# AVRProgrammer.net
KiCad netlist of a schematic drawn in EAGLE
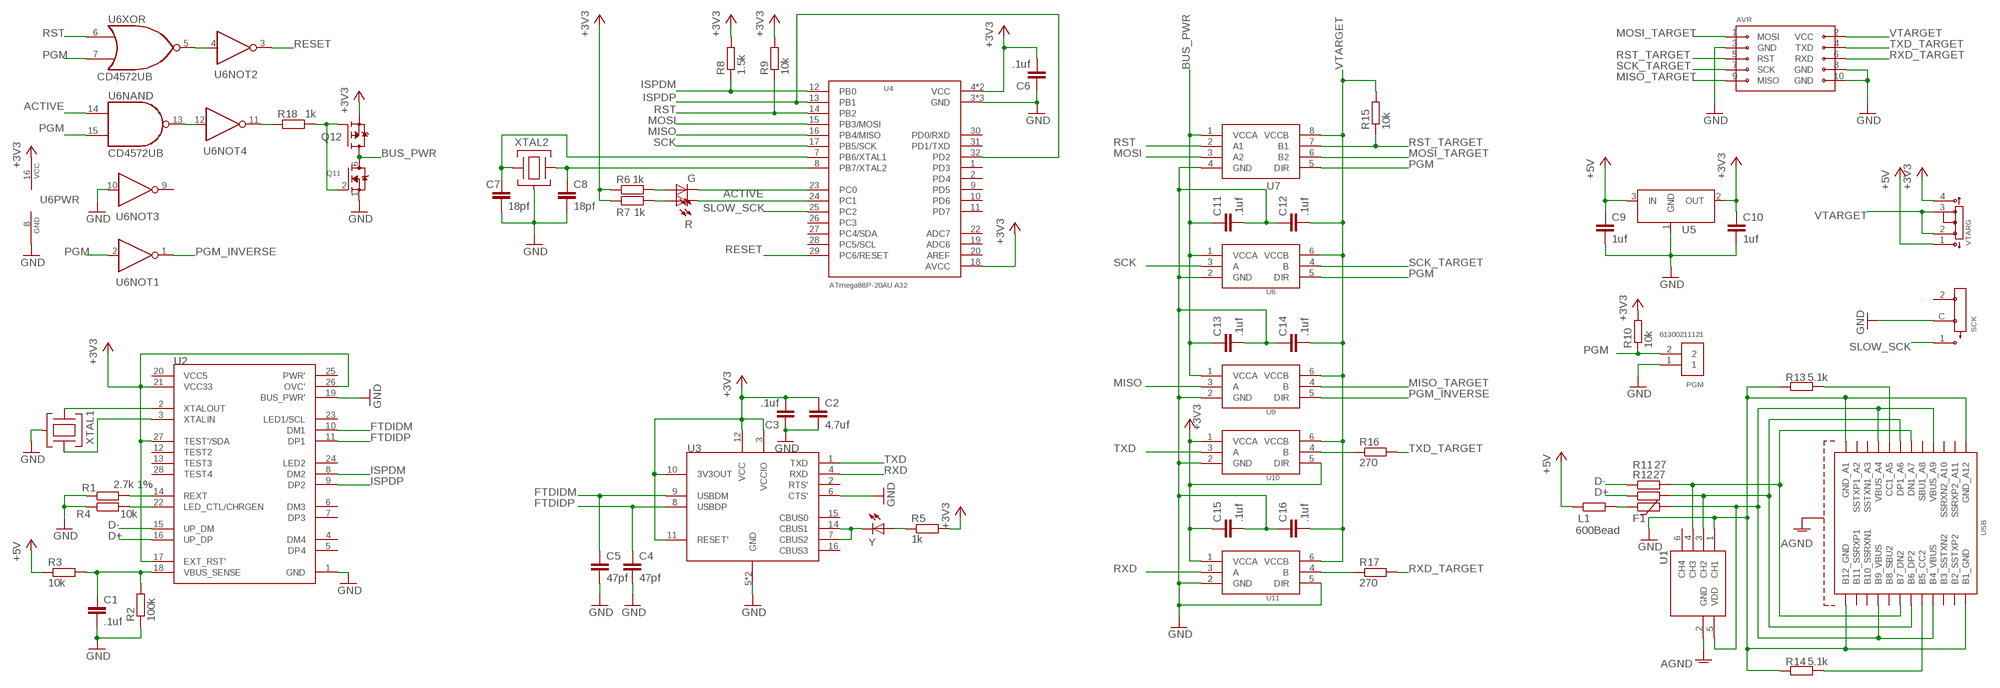
[diagram p0: schematic, sheet 1]

(export (version "E")
  (design (tool "Eeschema 10.0.6"))
  (components
    (comp (ref "AVR")
      (value "10PIN_ISP10PIN_ISP_RT")
      (footprint "eagle-import:10PIN_ISP_RT")
      (libsource (lib "eagle-import") (part "10PIN_ISP10PIN_ISP_RT"))
    )
    (comp (ref "C1")
      (value ".1uf")
      (footprint "eagle-import:C0805")
      (libsource (lib "eagle-import") (part "C-EUC0805"))
    )
    (comp (ref "C2")
      (value "4.7uf")
      (footprint "eagle-import:C0805")
      (libsource (lib "eagle-import") (part "C-EUC0805"))
    )
    (comp (ref "C3")
      (value ".1uf")
      (footprint "eagle-import:C0805")
      (libsource (lib "eagle-import") (part "C-EUC0805"))
    )
    (comp (ref "C4")
      (value "47pf")
      (footprint "eagle-import:C0805")
      (libsource (lib "eagle-import") (part "C-EUC0805"))
    )
    (comp (ref "C5")
      (value "47pf")
      (footprint "eagle-import:C0805")
      (libsource (lib "eagle-import") (part "C-EUC0805"))
    )
    (comp (ref "C6")
      (value ".1uf")
      (footprint "eagle-import:C0805")
      (libsource (lib "eagle-import") (part "C-EUC0805"))
    )
    (comp (ref "C7")
      (value "18pf")
      (footprint "eagle-import:C0805")
      (libsource (lib "eagle-import") (part "C-EUC0805"))
    )
    (comp (ref "C8")
      (value "18pf")
      (footprint "eagle-import:C0805")
      (libsource (lib "eagle-import") (part "C-EUC0805"))
    )
    (comp (ref "C9")
      (value "1uf")
      (footprint "eagle-import:C0805")
      (libsource (lib "eagle-import") (part "C-EUC0805"))
    )
    (comp (ref "C10")
      (value "1uf")
      (footprint "eagle-import:C0805")
      (libsource (lib "eagle-import") (part "C-EUC0805"))
    )
    (comp (ref "C11")
      (value ".1uf")
      (footprint "eagle-import:C0805")
      (libsource (lib "eagle-import") (part "C-EUC0805"))
    )
    (comp (ref "C12")
      (value ".1uf")
      (footprint "eagle-import:C0805")
      (libsource (lib "eagle-import") (part "C-EUC0805"))
    )
    (comp (ref "C13")
      (value ".1uf")
      (footprint "eagle-import:C0805")
      (libsource (lib "eagle-import") (part "C-EUC0805"))
    )
    (comp (ref "C14")
      (value ".1uf")
      (footprint "eagle-import:C0805")
      (libsource (lib "eagle-import") (part "C-EUC0805"))
    )
    (comp (ref "C15")
      (value ".1uf")
      (footprint "eagle-import:C0805")
      (libsource (lib "eagle-import") (part "C-EUC0805"))
    )
    (comp (ref "C16")
      (value ".1uf")
      (footprint "eagle-import:C0805")
      (libsource (lib "eagle-import") (part "C-EUC0805"))
    )
    (comp (ref "F1")
      (value "MF-PSHT035KX-2")
      (footprint "eagle-import:FUSC2113X120N")
      (libsource (lib "eagle-import") (part "PTC0805"))
    )
    (comp (ref "G")
      (value "SM0805GCL")
      (footprint "eagle-import:CHIPLED_0805")
      (libsource (lib "eagle-import") (part "LEDCHIPLED_0805"))
    )
    (comp (ref "L1")
      (value "600Bead")
      (footprint "eagle-import:M0805")
      (libsource (lib "eagle-import") (part "rcl_334_R-EU_M0805"))
    )
    (comp (ref "PGM")
      (value "61300211121")
      (footprint "eagle-import:61300211121")
      (fields
        (field (name "DIGI_KEY_PART_NUMBER") "732-5315-ND")
        (field (name "MANUFACTURER") "Wurth Electronics Inc.")
        (field (name "CREATED_BY") "PCBLayout.com")
      )
      (libsource (lib "eagle-import") (part "61300211121"))
    )
    (comp (ref "Q1")
      (value "SI1016CX-T1-GE3SOT-563F")
      (footprint "eagle-import:SOTFL50P160X60-6N")
      (libsource (lib "eagle-import") (part "SI1016CX-T1-GE3SOT-563F"))
    )
    (comp (ref "R")
      (value "SM0805HCL")
      (footprint "eagle-import:CHIPLED_0805")
      (libsource (lib "eagle-import") (part "LEDCHIPLED_0805"))
    )
    (comp (ref "R1")
      (value "2.7k 1%")
      (footprint "eagle-import:M0805")
      (libsource (lib "eagle-import") (part "rcl_334_R-EU_M0805"))
    )
    (comp (ref "R2")
      (value "100k")
      (footprint "eagle-import:M0805")
      (libsource (lib "eagle-import") (part "rcl_334_R-EU_M0805"))
    )
    (comp (ref "R3")
      (value "10k")
      (footprint "eagle-import:M0805")
      (libsource (lib "eagle-import") (part "rcl_334_R-EU_M0805"))
    )
    (comp (ref "R4")
      (value "10k")
      (footprint "eagle-import:M0805")
      (libsource (lib "eagle-import") (part "R-EU_M0805"))
    )
    (comp (ref "R5")
      (value "1k")
      (footprint "eagle-import:M0805")
      (libsource (lib "eagle-import") (part "rcl_334_R-EU_M0805"))
    )
    (comp (ref "R6")
      (value "1k")
      (footprint "eagle-import:M0805")
      (libsource (lib "eagle-import") (part "rcl_334_R-EU_M0805"))
    )
    (comp (ref "R7")
      (value "1k")
      (footprint "eagle-import:M0805")
      (libsource (lib "eagle-import") (part "rcl_334_R-EU_M0805"))
    )
    (comp (ref "R8")
      (value "1.5k")
      (footprint "eagle-import:M0805")
      (libsource (lib "eagle-import") (part "R-EU_M0805"))
    )
    (comp (ref "R9")
      (value "10k")
      (footprint "eagle-import:M0805")
      (libsource (lib "eagle-import") (part "R-EU_M0805"))
    )
    (comp (ref "R10")
      (value "10k")
      (footprint "eagle-import:R0805")
      (libsource (lib "eagle-import") (part "rcl_334_R-EU_R0805"))
    )
    (comp (ref "R11")
      (value "27")
      (footprint "eagle-import:M0805")
      (libsource (lib "eagle-import") (part "rcl_334_R-EU_M0805"))
    )
    (comp (ref "R12")
      (value "27")
      (footprint "eagle-import:M0805")
      (libsource (lib "eagle-import") (part "rcl_334_R-EU_M0805"))
    )
    (comp (ref "R13")
      (value "5.1k")
      (footprint "eagle-import:M0805")
      (libsource (lib "eagle-import") (part "rcl_334_R-EU_M0805"))
    )
    (comp (ref "R14")
      (value "5.1k")
      (footprint "eagle-import:M0805")
      (libsource (lib "eagle-import") (part "rcl_334_R-EU_M0805"))
    )
    (comp (ref "R15")
      (value "10k")
      (footprint "eagle-import:R0805")
      (libsource (lib "eagle-import") (part "rcl_334_R-EU_R0805"))
    )
    (comp (ref "R16")
      (value "270")
      (footprint "eagle-import:R0805")
      (libsource (lib "eagle-import") (part "rcl_334_R-EU_R0805"))
    )
    (comp (ref "R17")
      (value "270")
      (footprint "eagle-import:R0805")
      (libsource (lib "eagle-import") (part "rcl_334_R-EU_R0805"))
    )
    (comp (ref "R18")
      (value "1k")
      (footprint "eagle-import:M0805")
      (libsource (lib "eagle-import") (part "rcl_334_R-EU_M0805"))
    )
    (comp (ref "SCK")
      (value "SPDT_SWITCH")
      (footprint "eagle-import:SSAJ110100")
      (libsource (lib "eagle-import") (part "SPDT_SWITCH"))
    )
    (comp (ref "U1")
      (value "D5V0F4U6SO")
      (footprint "eagle-import:SOT95P280X145-6")
      (libsource (lib "eagle-import") (part "D5V0F4U6SO"))
    )
    (comp (ref "U2")
      (value "XR22404SSOP28")
      (footprint "eagle-import:SOP63P599X173-28")
      (libsource (lib "eagle-import") (part "XR22404SSOP28"))
    )
    (comp (ref "U3")
      (value "FT230XSSOP16")
      (footprint "eagle-import:SOP63P599X175-16")
      (libsource (lib "eagle-import") (part "FT230XSSOP16"))
    )
    (comp (ref "U4")
      (value "ATmega88P-20AU A32")
      (footprint "eagle-import:QFP80P887X887X120-32")
      (libsource (lib "eagle-import") (part "ATMEGA328P-AUTQFP-32"))
    )
    (comp (ref "U5")
      (value "AZ1117E-3.3SOT-223")
      (footprint "eagle-import:SOT230P700X180-4")
      (libsource (lib "eagle-import") (part "AZ1117E-3.3SOT-223"))
    )
    (comp (ref "U6")
      (value "CD4572UB")
      (footprint "eagle-import:SOP65P640X110-16N")
      (libsource (lib "eagle-import") (part "CD4572UB"))
    )
    (comp (ref "U7")
      (value "SN74LVC2T45-Q1VSSOP-8")
      (footprint "eagle-import:SOP50P310X90-8N")
      (libsource (lib "eagle-import") (part "SN74LVC2T45-Q1VSSOP-8"))
    )
    (comp (ref "U8")
      (value "SN74LVC1T45DRL")
      (footprint "eagle-import:SOTFL50P160X60-6N")
      (libsource (lib "eagle-import") (part "SN74LVC1T45DRL"))
    )
    (comp (ref "U9")
      (value "SN74LVC1T45DRL")
      (footprint "eagle-import:SOTFL50P160X60-6N")
      (libsource (lib "eagle-import") (part "SN74LVC1T45DRL"))
    )
    (comp (ref "U10")
      (value "SN74LVC1T45DRL")
      (footprint "eagle-import:SOTFL50P160X60-6N")
      (libsource (lib "eagle-import") (part "SN74LVC1T45DRL"))
    )
    (comp (ref "U11")
      (value "SN74LVC1T45DRL")
      (footprint "eagle-import:SOTFL50P160X60-6N")
      (libsource (lib "eagle-import") (part "SN74LVC1T45DRL"))
    )
    (comp (ref "USB")
      (value "USBC_FEMALEUJ31-CH-G2-SMT-TR")
      (footprint "eagle-import:USBC_UJ31-CH-G2-SMT-TR")
      (libsource (lib "eagle-import") (part "USBC_FEMALEUJ31-CH-G2-SMT-TR"))
    )
    (comp (ref "VTARG")
      (value "SP3T_SWITCH")
      (footprint "eagle-import:EG1315AA")
      (libsource (lib "eagle-import") (part "SP3T_SWITCH"))
    )
    (comp (ref "XTAL1")
      (value "XTAL_ABM8AIG")
      (footprint "eagle-import:XTAL_SMT_3.2X2.5")
      (libsource (lib "eagle-import") (part "XTAL_ABM8AIG"))
    )
    (comp (ref "XTAL2")
      (value "XTAL_ABM8AIG")
      (footprint "eagle-import:XTAL_SMT_3.2X2.5")
      (libsource (lib "eagle-import") (part "XTAL_ABM8AIG"))
    )
    (comp (ref "Y")
      (value "LEDCHIPLED_0805")
      (footprint "eagle-import:CHIPLED_0805")
      (libsource (lib "eagle-import") (part "LEDCHIPLED_0805"))
    )
  )
  (nets
    (net (code "1") (name "+3V3") (class "Default")
      (node (ref "C10") (pin "1") (pinfunction "1_1") (pintype "passive"))
      (node (ref "C15") (pin "1") (pinfunction "1_1") (pintype "passive"))
      (node (ref "C2") (pin "1") (pinfunction "1_1") (pintype "passive"))
      (node (ref "C3") (pin "2") (pinfunction "2_2") (pintype "passive"))
      (node (ref "C6") (pin "2") (pinfunction "2_2") (pintype "passive"))
      (node (ref "Q1") (pin "4") (pinfunction "S_4") (pintype "passive"))
      (node (ref "R10") (pin "2") (pinfunction "2_2") (pintype "passive"))
      (node (ref "R5") (pin "2") (pinfunction "2_2") (pintype "passive"))
      (node (ref "R6") (pin "1") (pinfunction "1_1") (pintype "passive"))
      (node (ref "R7") (pin "1") (pinfunction "1_1") (pintype "passive"))
      (node (ref "R8") (pin "2") (pinfunction "2_2") (pintype "passive"))
      (node (ref "R9") (pin "2") (pinfunction "2_2") (pintype "passive"))
      (node (ref "U10") (pin "1") (pinfunction "VCCA_1") (pintype "power_in"))
      (node (ref "U10") (pin "5") (pinfunction "DIR_5") (pintype "bidirectional"))
      (node (ref "U11") (pin "1") (pinfunction "VCCA_1") (pintype "power_in"))
      (node (ref "U2") (pin "17") (pinfunction "EXT_RST'_17") (pintype "bidirectional"))
      (node (ref "U2") (pin "21") (pinfunction "VCC33_21") (pintype "bidirectional"))
      (node (ref "U2") (pin "26") (pinfunction "OVC'_26") (pintype "bidirectional"))
      (node (ref "U2") (pin "27") (pinfunction "TEST'/SDA_27") (pintype "bidirectional"))
      (node (ref "U3") (pin "10") (pinfunction "3V3OUT_10") (pintype "bidirectional"))
      (node (ref "U3") (pin "11") (pinfunction "RESET'_11") (pintype "bidirectional"))
      (node (ref "U3") (pin "12") (pinfunction "VCC_12") (pintype "power_in"))
      (node (ref "U3") (pin "3") (pinfunction "VCCIO_3") (pintype "power_in"))
      (node (ref "U4") (pin "18") (pinfunction "AVCC_18") (pintype "power_in"))
      (node (ref "U4") (pin "4") (pinfunction "VCC_4") (pintype "power_in"))
      (node (ref "U4") (pin "6") (pinfunction "VCC_6") (pintype "power_in"))
      (node (ref "U5") (pin "2") (pinfunction "OUT_2") (pintype "power_in"))
      (node (ref "U6") (pin "16") (pinfunction "VCC_16") (pintype "power_in"))
      (node (ref "VTARG") (pin "4") (pinfunction "4_4") (pintype "bidirectional"))
    )
    (net (code "2") (name "+5V") (class "Default")
      (node (ref "C9") (pin "1") (pinfunction "1_1") (pintype "passive"))
      (node (ref "L1") (pin "1") (pinfunction "1_1") (pintype "passive"))
      (node (ref "R3") (pin "1") (pinfunction "1_1") (pintype "passive"))
      (node (ref "U5") (pin "3") (pinfunction "IN_3") (pintype "power_in"))
      (node (ref "VTARG") (pin "1") (pinfunction "1_1") (pintype "bidirectional"))
    )
    (net (code "3") (name "/ACTIVE") (class "Default")
      (node (ref "R") (pin "C") (pinfunction "C_C") (pintype "passive"))
      (node (ref "U4") (pin "24") (pinfunction "PC1_24") (pintype "bidirectional"))
      (node (ref "U6") (pin "14") (pinfunction "I0_14") (pintype "input"))
    )
    (net (code "4") (name "/BUS_PWR") (class "Default")
      (node (ref "C11") (pin "1") (pinfunction "1_1") (pintype "passive"))
      (node (ref "C13") (pin "1") (pinfunction "1_1") (pintype "passive"))
      (node (ref "Q1") (pin "3") (pinfunction "D_3") (pintype "passive"))
      (node (ref "Q1") (pin "6") (pinfunction "D_6") (pintype "bidirectional"))
      (node (ref "U7") (pin "1") (pinfunction "VCCA_1") (pintype "power_in"))
      (node (ref "U8") (pin "1") (pinfunction "VCCA_1") (pintype "power_in"))
      (node (ref "U9") (pin "1") (pinfunction "VCCA_1") (pintype "power_in"))
    )
    (net (code "5") (name "/D+") (class "Default")
      (node (ref "R12") (pin "1") (pinfunction "1_1") (pintype "passive"))
      (node (ref "U2") (pin "16") (pinfunction "UP_DP_16") (pintype "bidirectional"))
    )
    (net (code "6") (name "/D-") (class "Default")
      (node (ref "R11") (pin "1") (pinfunction "1_1") (pintype "passive"))
      (node (ref "U2") (pin "15") (pinfunction "UP_DM_15") (pintype "bidirectional"))
    )
    (net (code "7") (name "/FTDIDM") (class "Default")
      (node (ref "C5") (pin "1") (pinfunction "1_1") (pintype "passive"))
      (node (ref "U2") (pin "10") (pinfunction "DM1_10") (pintype "bidirectional"))
      (node (ref "U3") (pin "9") (pinfunction "USBDM_9") (pintype "bidirectional"))
    )
    (net (code "8") (name "/FTDIDP") (class "Default")
      (node (ref "C4") (pin "1") (pinfunction "1_1") (pintype "passive"))
      (node (ref "U2") (pin "11") (pinfunction "DP1_11") (pintype "bidirectional"))
      (node (ref "U3") (pin "8") (pinfunction "USBDP_8") (pintype "bidirectional"))
    )
    (net (code "9") (name "/ISPDM") (class "Default")
      (node (ref "R8") (pin "1") (pinfunction "1_1") (pintype "passive"))
      (node (ref "U2") (pin "8") (pinfunction "DM2_8") (pintype "bidirectional"))
      (node (ref "U4") (pin "12") (pinfunction "PB0_12") (pintype "bidirectional"))
    )
    (net (code "10") (name "/ISPDP") (class "Default")
      (node (ref "U2") (pin "9") (pinfunction "DP2_9") (pintype "bidirectional"))
      (node (ref "U4") (pin "13") (pinfunction "PB1_13") (pintype "bidirectional"))
      (node (ref "U4") (pin "32") (pinfunction "PD2_32") (pintype "bidirectional"))
    )
    (net (code "11") (name "/MISO") (class "Default")
      (node (ref "U4") (pin "16") (pinfunction "PB4/MISO_16") (pintype "bidirectional"))
      (node (ref "U9") (pin "3") (pinfunction "A_3") (pintype "bidirectional"))
    )
    (net (code "12") (name "/MISO_TARGET") (class "Default")
      (node (ref "AVR") (pin "9") (pinfunction "MISO_9") (pintype "bidirectional"))
      (node (ref "U9") (pin "4") (pinfunction "B_4") (pintype "bidirectional"))
    )
    (net (code "13") (name "/MOSI") (class "Default")
      (node (ref "U4") (pin "15") (pinfunction "PB3/MOSI_15") (pintype "bidirectional"))
      (node (ref "U7") (pin "3") (pinfunction "A2_3") (pintype "bidirectional"))
    )
    (net (code "14") (name "/MOSI_TARGET") (class "Default")
      (node (ref "AVR") (pin "1") (pinfunction "MOSI_1") (pintype "bidirectional"))
      (node (ref "U7") (pin "6") (pinfunction "B2_6") (pintype "bidirectional"))
    )
    (net (code "15") (name "/PGM") (class "Default")
      (node (ref "PGM") (pin "2") (pinfunction "2_2") (pintype "passive"))
      (node (ref "R10") (pin "1") (pinfunction "1_1") (pintype "passive"))
      (node (ref "U6") (pin "15") (pinfunction "I1_15") (pintype "input"))
      (node (ref "U6") (pin "2") (pinfunction "A_2") (pintype "bidirectional"))
      (node (ref "U6") (pin "7") (pinfunction "I1_7") (pintype "input"))
      (node (ref "U7") (pin "5") (pinfunction "DIR_5") (pintype "bidirectional"))
      (node (ref "U8") (pin "5") (pinfunction "DIR_5") (pintype "bidirectional"))
    )
    (net (code "16") (name "/PGM_INVERSE") (class "Default")
      (node (ref "U6") (pin "1") (pinfunction "Y_1") (pintype "bidirectional"))
      (node (ref "U9") (pin "5") (pinfunction "DIR_5") (pintype "bidirectional"))
    )
    (net (code "17") (name "/RESET") (class "Default")
      (node (ref "U4") (pin "29") (pinfunction "PC6/RESET_29") (pintype "bidirectional"))
      (node (ref "U6") (pin "3") (pinfunction "Y_3") (pintype "bidirectional"))
    )
    (net (code "18") (name "/RST") (class "Default")
      (node (ref "R9") (pin "1") (pinfunction "1_1") (pintype "passive"))
      (node (ref "U4") (pin "14") (pinfunction "PB2_14") (pintype "bidirectional"))
      (node (ref "U6") (pin "6") (pinfunction "I0_6") (pintype "input"))
      (node (ref "U7") (pin "2") (pinfunction "A1_2") (pintype "bidirectional"))
    )
    (net (code "19") (name "/RST_TARGET") (class "Default")
      (node (ref "AVR") (pin "5") (pinfunction "RST_5") (pintype "bidirectional"))
      (node (ref "R15") (pin "1") (pinfunction "1_1") (pintype "passive"))
      (node (ref "U7") (pin "7") (pinfunction "B1_7") (pintype "bidirectional"))
    )
    (net (code "20") (name "/RXD") (class "Default")
      (node (ref "U11") (pin "3") (pinfunction "A_3") (pintype "bidirectional"))
      (node (ref "U3") (pin "4") (pinfunction "RXD_4") (pintype "bidirectional"))
    )
    (net (code "21") (name "/RXD_TARGET") (class "Default")
      (node (ref "AVR") (pin "6") (pinfunction "RXD_6") (pintype "bidirectional"))
      (node (ref "R17") (pin "2") (pinfunction "2_2") (pintype "passive"))
    )
    (net (code "22") (name "/SCK") (class "Default")
      (node (ref "U4") (pin "17") (pinfunction "PB5/SCK_17") (pintype "bidirectional"))
      (node (ref "U8") (pin "3") (pinfunction "A_3") (pintype "bidirectional"))
    )
    (net (code "23") (name "/SCK_TARGET") (class "Default")
      (node (ref "AVR") (pin "7") (pinfunction "SCK_7") (pintype "bidirectional"))
      (node (ref "U8") (pin "4") (pinfunction "B_4") (pintype "bidirectional"))
    )
    (net (code "24") (name "/SLOW_SCK") (class "Default")
      (node (ref "SCK") (pin "1") (pinfunction "1_1") (pintype "bidirectional"))
      (node (ref "U4") (pin "25") (pinfunction "PC2_25") (pintype "bidirectional"))
    )
    (net (code "25") (name "/TXD") (class "Default")
      (node (ref "U10") (pin "3") (pinfunction "A_3") (pintype "bidirectional"))
      (node (ref "U3") (pin "1") (pinfunction "TXD_1") (pintype "bidirectional"))
    )
    (net (code "26") (name "/TXD_TARGET") (class "Default")
      (node (ref "AVR") (pin "4") (pinfunction "TXD_4") (pintype "bidirectional"))
      (node (ref "R16") (pin "2") (pinfunction "2_2") (pintype "passive"))
    )
    (net (code "27") (name "/VCC5") (class "Default")
      (node (ref "U2") (pin "20") (pinfunction "VCC5_20") (pintype "power_in"))
    )
    (net (code "28") (name "/VTARGET") (class "Default")
      (node (ref "AVR") (pin "2") (pinfunction "VCC_2") (pintype "bidirectional"))
      (node (ref "C12") (pin "2") (pinfunction "2_2") (pintype "passive"))
      (node (ref "C14") (pin "2") (pinfunction "2_2") (pintype "passive"))
      (node (ref "C16") (pin "2") (pinfunction "2_2") (pintype "passive"))
      (node (ref "R15") (pin "2") (pinfunction "2_2") (pintype "passive"))
      (node (ref "U10") (pin "6") (pinfunction "VCCB_6") (pintype "power_in"))
      (node (ref "U11") (pin "6") (pinfunction "VCCB_6") (pintype "power_in"))
      (node (ref "U7") (pin "8") (pinfunction "VCCB_8") (pintype "power_in"))
      (node (ref "U8") (pin "6") (pinfunction "VCCB_6") (pintype "power_in"))
      (node (ref "U9") (pin "6") (pinfunction "VCCB_6") (pintype "power_in"))
      (node (ref "VTARG") (pin "2") (pinfunction "2_2") (pintype "bidirectional"))
      (node (ref "VTARG") (pin "3") (pinfunction "C_3") (pintype "bidirectional"))
    )
    (net (code "29") (name "AGND") (class "Default")
      (node (ref "U1") (pin "2") (pinfunction "GND_2") (pintype "bidirectional"))
      (node (ref "USB") (pin "SHD$1") (pinfunction "SHLD_SHD$1") (pintype "power_in"))
      (node (ref "USB") (pin "SHD$2") (pinfunction "SHLD_SHD$2") (pintype "power_in"))
      (node (ref "USB") (pin "SHD$3") (pinfunction "SHLD_SHD$3") (pintype "power_in"))
      (node (ref "USB") (pin "SHD$4") (pinfunction "SHLD_SHD$4") (pintype "power_in"))
    )
    (net (code "30") (name "GND") (class "Default")
      (node (ref "AVR") (pin "10") (pinfunction "GND_10") (pintype "bidirectional"))
      (node (ref "AVR") (pin "3") (pinfunction "GND_3") (pintype "bidirectional"))
      (node (ref "AVR") (pin "8") (pinfunction "GND_8") (pintype "bidirectional"))
      (node (ref "C1") (pin "2") (pinfunction "2_2") (pintype "passive"))
      (node (ref "C10") (pin "2") (pinfunction "2_2") (pintype "passive"))
      (node (ref "C11") (pin "2") (pinfunction "2_2") (pintype "passive"))
      (node (ref "C12") (pin "1") (pinfunction "1_1") (pintype "passive"))
      (node (ref "C13") (pin "2") (pinfunction "2_2") (pintype "passive"))
      (node (ref "C14") (pin "1") (pinfunction "1_1") (pintype "passive"))
      (node (ref "C15") (pin "2") (pinfunction "2_2") (pintype "passive"))
      (node (ref "C16") (pin "1") (pinfunction "1_1") (pintype "passive"))
      (node (ref "C2") (pin "2") (pinfunction "2_2") (pintype "passive"))
      (node (ref "C3") (pin "1") (pinfunction "1_1") (pintype "passive"))
      (node (ref "C4") (pin "2") (pinfunction "2_2") (pintype "passive"))
      (node (ref "C5") (pin "2") (pinfunction "2_2") (pintype "passive"))
      (node (ref "C6") (pin "1") (pinfunction "1_1") (pintype "passive"))
      (node (ref "C7") (pin "2") (pinfunction "2_2") (pintype "passive"))
      (node (ref "C8") (pin "2") (pinfunction "2_2") (pintype "passive"))
      (node (ref "C9") (pin "2") (pinfunction "2_2") (pintype "passive"))
      (node (ref "PGM") (pin "1") (pinfunction "1_1") (pintype "passive"))
      (node (ref "Q1") (pin "1") (pinfunction "S_1") (pintype "bidirectional"))
      (node (ref "R1") (pin "1") (pinfunction "1_1") (pintype "passive"))
      (node (ref "R13") (pin "1") (pinfunction "1_1") (pintype "passive"))
      (node (ref "R14") (pin "1") (pinfunction "1_1") (pintype "passive"))
      (node (ref "R2") (pin "1") (pinfunction "1_1") (pintype "passive"))
      (node (ref "R4") (pin "1") (pinfunction "1_1") (pintype "passive"))
      (node (ref "SCK") (pin "C") (pinfunction "C_C") (pintype "bidirectional"))
      (node (ref "U1") (pin "1") (pinfunction "CH1_1") (pintype "bidirectional"))
      (node (ref "U10") (pin "2") (pinfunction "GND_2") (pintype "power_in"))
      (node (ref "U11") (pin "2") (pinfunction "GND_2") (pintype "power_in"))
      (node (ref "U11") (pin "5") (pinfunction "DIR_5") (pintype "bidirectional"))
      (node (ref "U2") (pin "1") (pinfunction "GND_1") (pintype "power_in"))
      (node (ref "U2") (pin "19") (pinfunction "BUS_PWR'_19") (pintype "bidirectional"))
      (node (ref "U3") (pin "13") (pinfunction "GND_13") (pintype "power_in"))
      (node (ref "U3") (pin "5") (pinfunction "GND_5") (pintype "power_in"))
      (node (ref "U3") (pin "6") (pinfunction "CTS'_6") (pintype "bidirectional"))
      (node (ref "U4") (pin "21") (pinfunction "GND_21") (pintype "power_in"))
      (node (ref "U4") (pin "3") (pinfunction "GND_3") (pintype "power_in"))
      (node (ref "U4") (pin "5") (pinfunction "GND_5") (pintype "power_in"))
      (node (ref "U5") (pin "1") (pinfunction "GND_1") (pintype "power_in"))
      (node (ref "U6") (pin "10") (pinfunction "A_10") (pintype "bidirectional"))
      (node (ref "U6") (pin "8") (pinfunction "GND_8") (pintype "power_in"))
      (node (ref "U7") (pin "4") (pinfunction "GND_4") (pintype "power_in"))
      (node (ref "U8") (pin "2") (pinfunction "GND_2") (pintype "power_in"))
      (node (ref "U9") (pin "2") (pinfunction "GND_2") (pintype "power_in"))
      (node (ref "USB") (pin "A1") (pinfunction "GND_A1_A1") (pintype "power_in"))
      (node (ref "USB") (pin "A12") (pinfunction "GND_A12_A12") (pintype "power_in"))
      (node (ref "USB") (pin "B1") (pinfunction "B1_GND_B1") (pintype "power_in"))
      (node (ref "USB") (pin "B12") (pinfunction "B12_GND_B12") (pintype "power_in"))
      (node (ref "XTAL1") (pin "2") (pinfunction "CASE_2") (pintype "bidirectional"))
      (node (ref "XTAL1") (pin "4") (pinfunction "CASE_4") (pintype "bidirectional"))
      (node (ref "XTAL2") (pin "2") (pinfunction "CASE_2") (pintype "bidirectional"))
      (node (ref "XTAL2") (pin "4") (pinfunction "CASE_4") (pintype "bidirectional"))
    )
    (net (code "31") (name "Net-(F1-Pad1)") (class "Default")
      (node (ref "F1") (pin "1") (pinfunction "1_1") (pintype "passive"))
      (node (ref "L1") (pin "2") (pinfunction "2_2") (pintype "passive"))
    )
    (net (code "32") (name "Net-(G-PadA)") (class "Default")
      (node (ref "G") (pin "A") (pinfunction "A_A") (pintype "passive"))
      (node (ref "R6") (pin "2") (pinfunction "2_2") (pintype "passive"))
    )
    (net (code "33") (name "Net-(Q1A-G)") (class "Default")
      (node (ref "Q1") (pin "2") (pinfunction "G_2") (pintype "bidirectional"))
      (node (ref "Q1") (pin "5") (pinfunction "G_5") (pintype "passive"))
      (node (ref "R18") (pin "2") (pinfunction "2_2") (pintype "passive"))
    )
    (net (code "34") (name "Net-(R-PadA)") (class "Default")
      (node (ref "R") (pin "A") (pinfunction "A_A") (pintype "passive"))
      (node (ref "R7") (pin "2") (pinfunction "2_2") (pintype "passive"))
    )
    (net (code "35") (name "Net-(R5-Pad1)") (class "Default")
      (node (ref "R5") (pin "1") (pinfunction "1_1") (pintype "passive"))
      (node (ref "Y") (pin "A") (pinfunction "A_A") (pintype "passive"))
    )
    (net (code "36") (name "Net-(U1-CH2)") (class "Default")
      (node (ref "R12") (pin "2") (pinfunction "2_2") (pintype "passive"))
      (node (ref "U1") (pin "3") (pinfunction "CH2_3") (pintype "bidirectional"))
      (node (ref "USB") (pin "A6") (pinfunction "DP1_A6_A6") (pintype "bidirectional"))
      (node (ref "USB") (pin "B6") (pinfunction "B6_DP2_B6") (pintype "bidirectional"))
    )
    (net (code "37") (name "Net-(U1-CH3)") (class "Default")
      (node (ref "R11") (pin "2") (pinfunction "2_2") (pintype "passive"))
      (node (ref "U1") (pin "4") (pinfunction "CH3_4") (pintype "bidirectional"))
      (node (ref "USB") (pin "A7") (pinfunction "DN1_A7_A7") (pintype "bidirectional"))
      (node (ref "USB") (pin "B7") (pinfunction "B7_DN2_B7") (pintype "bidirectional"))
    )
    (net (code "38") (name "Net-(U1-VDD)") (class "Default")
      (node (ref "F1") (pin "2") (pinfunction "2_2") (pintype "passive"))
      (node (ref "U1") (pin "5") (pinfunction "VDD_5") (pintype "bidirectional"))
      (node (ref "USB") (pin "A4") (pinfunction "VBUS_A4_A4") (pintype "power_in"))
      (node (ref "USB") (pin "A9") (pinfunction "VBUS_A9_A9") (pintype "power_in"))
      (node (ref "USB") (pin "B4") (pinfunction "B4_VBUS_B4") (pintype "power_in"))
      (node (ref "USB") (pin "B9") (pinfunction "B9_VBUS_B9") (pintype "power_in"))
    )
    (net (code "39") (name "Net-(U2-LED_CTL{slash}CHRGEN)") (class "Default")
      (node (ref "R4") (pin "2") (pinfunction "2_2") (pintype "passive"))
      (node (ref "U2") (pin "22") (pinfunction "LED_CTL/CHRGEN_22") (pintype "bidirectional"))
    )
    (net (code "40") (name "Net-(U2-REXT)") (class "Default")
      (node (ref "R1") (pin "2") (pinfunction "2_2") (pintype "passive"))
      (node (ref "U2") (pin "14") (pinfunction "REXT_14") (pintype "bidirectional"))
    )
    (net (code "41") (name "Net-(U2-VBUS_SENSE)") (class "Default")
      (node (ref "C1") (pin "1") (pinfunction "1_1") (pintype "passive"))
      (node (ref "R2") (pin "2") (pinfunction "2_2") (pintype "passive"))
      (node (ref "R3") (pin "2") (pinfunction "2_2") (pintype "passive"))
      (node (ref "U2") (pin "18") (pinfunction "VBUS_SENSE_18") (pintype "bidirectional"))
    )
    (net (code "42") (name "Net-(U2-XTALIN)") (class "Default")
      (node (ref "U2") (pin "3") (pinfunction "XTALIN_3") (pintype "bidirectional"))
      (node (ref "XTAL1") (pin "3") (pinfunction "P$2_3") (pintype "bidirectional"))
    )
    (net (code "43") (name "Net-(U2-XTALOUT)") (class "Default")
      (node (ref "U2") (pin "2") (pinfunction "XTALOUT_2") (pintype "bidirectional"))
      (node (ref "XTAL1") (pin "1") (pinfunction "P$1_1") (pintype "bidirectional"))
    )
    (net (code "44") (name "Net-(U3-CBUS1)") (class "Default")
      (node (ref "U3") (pin "14") (pinfunction "CBUS1_14") (pintype "bidirectional"))
      (node (ref "U3") (pin "7") (pinfunction "CBUS2_7") (pintype "bidirectional"))
      (node (ref "Y") (pin "C") (pinfunction "C_C") (pintype "passive"))
    )
    (net (code "45") (name "Net-(U4-PB6{slash}XTAL1)") (class "Default")
      (node (ref "C7") (pin "1") (pinfunction "1_1") (pintype "passive"))
      (node (ref "U4") (pin "7") (pinfunction "PB6/XTAL1_7") (pintype "bidirectional"))
      (node (ref "XTAL2") (pin "1") (pinfunction "P$1_1") (pintype "bidirectional"))
    )
    (net (code "46") (name "Net-(U4-PB7{slash}XTAL2)") (class "Default")
      (node (ref "C8") (pin "1") (pinfunction "1_1") (pintype "passive"))
      (node (ref "U4") (pin "8") (pinfunction "PB7/XTAL2_8") (pintype "bidirectional"))
      (node (ref "XTAL2") (pin "3") (pinfunction "P$2_3") (pintype "bidirectional"))
    )
    (net (code "47") (name "Net-(U4-PC0)") (class "Default")
      (node (ref "G") (pin "C") (pinfunction "C_C") (pintype "passive"))
      (node (ref "U4") (pin "23") (pinfunction "PC0_23") (pintype "bidirectional"))
    )
    (net (code "48") (name "Net-(U6A-O)") (class "Default")
      (node (ref "U6") (pin "12") (pinfunction "A_12") (pintype "bidirectional"))
      (node (ref "U6") (pin "13") (pinfunction "O_13") (pintype "output"))
    )
    (net (code "49") (name "Net-(U6C-A)") (class "Default")
      (node (ref "U6") (pin "4") (pinfunction "A_4") (pintype "bidirectional"))
      (node (ref "U6") (pin "5") (pinfunction "O_5") (pintype "output"))
    )
    (net (code "50") (name "Net-(U6E-Y)") (class "Default")
      (node (ref "R18") (pin "1") (pinfunction "1_1") (pintype "passive"))
      (node (ref "U6") (pin "11") (pinfunction "Y_11") (pintype "bidirectional"))
    )
    (net (code "51") (name "Net-(U10-B)") (class "Default")
      (node (ref "R16") (pin "1") (pinfunction "1_1") (pintype "passive"))
      (node (ref "U10") (pin "4") (pinfunction "B_4") (pintype "bidirectional"))
    )
    (net (code "52") (name "Net-(U11-B)") (class "Default")
      (node (ref "R17") (pin "1") (pinfunction "1_1") (pintype "passive"))
      (node (ref "U11") (pin "4") (pinfunction "B_4") (pintype "bidirectional"))
    )
    (net (code "53") (name "Net-(USB-B5_CC2)") (class "Default")
      (node (ref "R14") (pin "2") (pinfunction "2_2") (pintype "passive"))
      (node (ref "USB") (pin "B5") (pinfunction "B5_CC2_B5") (pintype "bidirectional"))
    )
    (net (code "54") (name "Net-(USB-CC1_A5)") (class "Default")
      (node (ref "R13") (pin "2") (pinfunction "2_2") (pintype "passive"))
      (node (ref "USB") (pin "A5") (pinfunction "CC1_A5_A5") (pintype "bidirectional"))
    )
    (net (code "55") (name "unconnected-(SCK-Pad2)") (class "Default")
      (node (ref "SCK") (pin "2") (pinfunction "2_2") (pintype "bidirectional"))
    )
    (net (code "56") (name "unconnected-(U1-CH4-Pad6)") (class "Default")
      (node (ref "U1") (pin "6") (pinfunction "CH4_6") (pintype "bidirectional"))
    )
    (net (code "57") (name "unconnected-(U2-DM3-Pad6)") (class "Default")
      (node (ref "U2") (pin "6") (pinfunction "DM3_6") (pintype "bidirectional"))
    )
    (net (code "58") (name "unconnected-(U2-DM4-Pad4)") (class "Default")
      (node (ref "U2") (pin "4") (pinfunction "DM4_4") (pintype "bidirectional"))
    )
    (net (code "59") (name "unconnected-(U2-DP3-Pad7)") (class "Default")
      (node (ref "U2") (pin "7") (pinfunction "DP3_7") (pintype "bidirectional"))
    )
    (net (code "60") (name "unconnected-(U2-DP4-Pad5)") (class "Default")
      (node (ref "U2") (pin "5") (pinfunction "DP4_5") (pintype "bidirectional"))
    )
    (net (code "61") (name "unconnected-(U2-LED1{slash}SCL-Pad23)") (class "Default")
      (node (ref "U2") (pin "23") (pinfunction "LED1/SCL_23") (pintype "bidirectional"))
    )
    (net (code "62") (name "unconnected-(U2-LED2-Pad24)") (class "Default")
      (node (ref "U2") (pin "24") (pinfunction "LED2_24") (pintype "bidirectional"))
    )
    (net (code "63") (name "unconnected-(U2-PWR'-Pad25)") (class "Default")
      (node (ref "U2") (pin "25") (pinfunction "PWR'_25") (pintype "bidirectional"))
    )
    (net (code "64") (name "unconnected-(U2-TEST2-Pad12)") (class "Default")
      (node (ref "U2") (pin "12") (pinfunction "TEST2_12") (pintype "bidirectional"))
    )
    (net (code "65") (name "unconnected-(U2-TEST3-Pad13)") (class "Default")
      (node (ref "U2") (pin "13") (pinfunction "TEST3_13") (pintype "bidirectional"))
    )
    (net (code "66") (name "unconnected-(U2-TEST4-Pad28)") (class "Default")
      (node (ref "U2") (pin "28") (pinfunction "TEST4_28") (pintype "bidirectional"))
    )
    (net (code "67") (name "unconnected-(U3-CBUS0-Pad15)") (class "Default")
      (node (ref "U3") (pin "15") (pinfunction "CBUS0_15") (pintype "bidirectional"))
    )
    (net (code "68") (name "unconnected-(U3-CBUS3-Pad16)") (class "Default")
      (node (ref "U3") (pin "16") (pinfunction "CBUS3_16") (pintype "bidirectional"))
    )
    (net (code "69") (name "unconnected-(U3-RTS'-Pad2)") (class "Default")
      (node (ref "U3") (pin "2") (pinfunction "RTS'_2") (pintype "bidirectional"))
    )
    (net (code "70") (name "unconnected-(U4-ADC6-Pad19)") (class "Default")
      (node (ref "U4") (pin "19") (pinfunction "ADC6_19") (pintype "bidirectional"))
    )
    (net (code "71") (name "unconnected-(U4-ADC7-Pad22)") (class "Default")
      (node (ref "U4") (pin "22") (pinfunction "ADC7_22") (pintype "bidirectional"))
    )
    (net (code "72") (name "unconnected-(U4-AREF-Pad20)") (class "Default")
      (node (ref "U4") (pin "20") (pinfunction "AREF_20") (pintype "bidirectional"))
    )
    (net (code "73") (name "unconnected-(U4-PC3-Pad26)") (class "Default")
      (node (ref "U4") (pin "26") (pinfunction "PC3_26") (pintype "bidirectional"))
    )
    (net (code "74") (name "unconnected-(U4-PC4{slash}SDA-Pad27)") (class "Default")
      (node (ref "U4") (pin "27") (pinfunction "PC4/SDA_27") (pintype "bidirectional"))
    )
    (net (code "75") (name "unconnected-(U4-PC5{slash}SCL-Pad28)") (class "Default")
      (node (ref "U4") (pin "28") (pinfunction "PC5/SCL_28") (pintype "bidirectional"))
    )
    (net (code "76") (name "unconnected-(U4-PD0{slash}RXD-Pad30)") (class "Default")
      (node (ref "U4") (pin "30") (pinfunction "PD0/RXD_30") (pintype "bidirectional"))
    )
    (net (code "77") (name "unconnected-(U4-PD1{slash}TXD-Pad31)") (class "Default")
      (node (ref "U4") (pin "31") (pinfunction "PD1/TXD_31") (pintype "bidirectional"))
    )
    (net (code "78") (name "unconnected-(U4-PD3-Pad1)") (class "Default")
      (node (ref "U4") (pin "1") (pinfunction "PD3_1") (pintype "bidirectional"))
    )
    (net (code "79") (name "unconnected-(U4-PD4-Pad2)") (class "Default")
      (node (ref "U4") (pin "2") (pinfunction "PD4_2") (pintype "bidirectional"))
    )
    (net (code "80") (name "unconnected-(U4-PD5-Pad9)") (class "Default")
      (node (ref "U4") (pin "9") (pinfunction "PD5_9") (pintype "bidirectional"))
    )
    (net (code "81") (name "unconnected-(U4-PD6-Pad10)") (class "Default")
      (node (ref "U4") (pin "10") (pinfunction "PD6_10") (pintype "bidirectional"))
    )
    (net (code "82") (name "unconnected-(U4-PD7-Pad11)") (class "Default")
      (node (ref "U4") (pin "11") (pinfunction "PD7_11") (pintype "bidirectional"))
    )
    (net (code "83") (name "unconnected-(U6D-Y-Pad9)") (class "Default")
      (node (ref "U6") (pin "9") (pinfunction "Y_9") (pintype "bidirectional"))
    )
    (net (code "84") (name "unconnected-(USB-B2_SSTXP2-PadB2)") (class "Default")
      (node (ref "USB") (pin "B2") (pinfunction "B2_SSTXP2_B2") (pintype "bidirectional"))
    )
    (net (code "85") (name "unconnected-(USB-B3_SSTXN2-PadB3)") (class "Default")
      (node (ref "USB") (pin "B3") (pinfunction "B3_SSTXN2_B3") (pintype "bidirectional"))
    )
    (net (code "86") (name "unconnected-(USB-B8_SBU2-PadB8)") (class "Default")
      (node (ref "USB") (pin "B8") (pinfunction "B8_SBU2_B8") (pintype "bidirectional"))
    )
    (net (code "87") (name "unconnected-(USB-B10_SSRXN1-PadB10)") (class "Default")
      (node (ref "USB") (pin "B10") (pinfunction "B10_SSRXN1_B10") (pintype "bidirectional"))
    )
    (net (code "88") (name "unconnected-(USB-B11_SSRXP1-PadB11)") (class "Default")
      (node (ref "USB") (pin "B11") (pinfunction "B11_SSRXP1_B11") (pintype "bidirectional"))
    )
    (net (code "89") (name "unconnected-(USB-SBU1_A8-PadA8)") (class "Default")
      (node (ref "USB") (pin "A8") (pinfunction "SBU1_A8_A8") (pintype "bidirectional"))
    )
    (net (code "90") (name "unconnected-(USB-SSRXN2_A10-PadA10)") (class "Default")
      (node (ref "USB") (pin "A10") (pinfunction "SSRXN2_A10_A10") (pintype "bidirectional"))
    )
    (net (code "91") (name "unconnected-(USB-SSRXP2_A11-PadA11)") (class "Default")
      (node (ref "USB") (pin "A11") (pinfunction "SSRXP2_A11_A11") (pintype "bidirectional"))
    )
    (net (code "92") (name "unconnected-(USB-SSTXN1_A3-PadA3)") (class "Default")
      (node (ref "USB") (pin "A3") (pinfunction "SSTXN1_A3_A3") (pintype "bidirectional"))
    )
    (net (code "93") (name "unconnected-(USB-SSTXP1_A2-PadA2)") (class "Default")
      (node (ref "USB") (pin "A2") (pinfunction "SSTXP1_A2_A2") (pintype "bidirectional"))
    )
  )
)
